# current_sensor.net
KiCad netlist of a schematic drawn in EAGLE
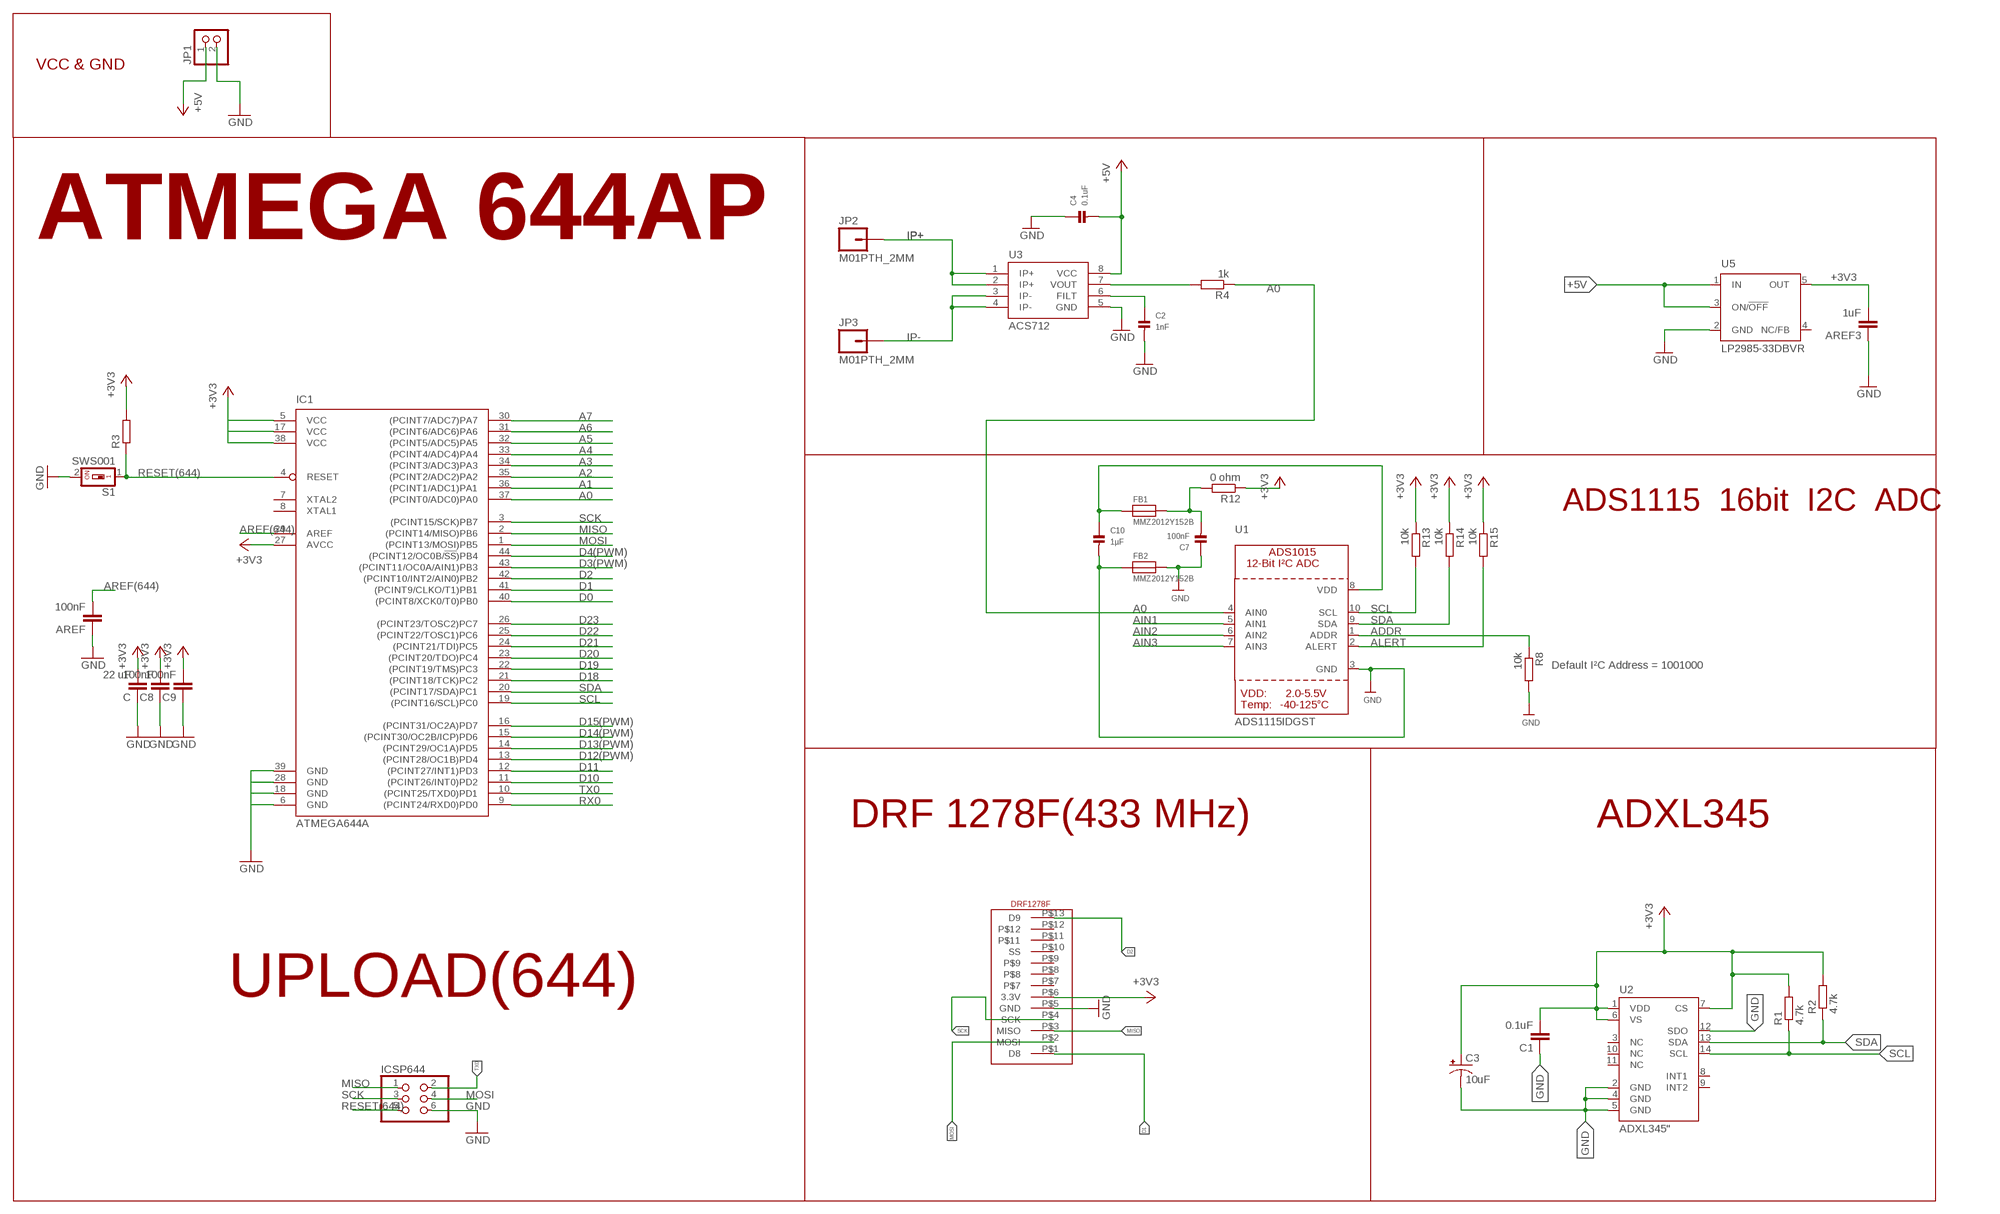
[diagram p0: schematic, sheet 1]

(export (version "E")
  (design (tool "Eeschema 10.0.6"))
  (components
    (comp (ref "AREF")
      (value "100nF")
      (footprint "eagle-import:C0805")
      (libsource (lib "eagle-import") (part "C-EUC0805"))
    )
    (comp (ref "AREF3")
      (value "1uF")
      (footprint "eagle-import:C0805")
      (libsource (lib "eagle-import") (part "C-EUC0805"))
    )
    (comp (ref "C")
      (value "22 uF")
      (footprint "eagle-import:C0805")
      (libsource (lib "eagle-import") (part "C-EUC0805"))
    )
    (comp (ref "C1")
      (value "0.1uF")
      (footprint "eagle-import:C0805")
      (libsource (lib "eagle-import") (part "C-EUC0805"))
    )
    (comp (ref "C2")
      (value "1nF")
      (footprint "eagle-import:0805")
      (libsource (lib "eagle-import") (part "CAP_CERAMIC0805"))
    )
    (comp (ref "C3")
      (value "10uF")
      (footprint "eagle-import:EIA3216")
      (libsource (lib "eagle-import") (part "CAP_POL1206"))
    )
    (comp (ref "C4")
      (value "0.1uF")
      (footprint "eagle-import:0805")
      (libsource (lib "eagle-import") (part "CAP_CERAMIC0805"))
    )
    (comp (ref "C7")
      (value "100nF")
      (footprint "eagle-import:0805")
      (libsource (lib "eagle-import") (part "CAP_CERAMIC0805"))
    )
    (comp (ref "C8")
      (value "100nF")
      (footprint "eagle-import:C0805")
      (libsource (lib "eagle-import") (part "C-EUC0805"))
    )
    (comp (ref "C9")
      (value "100nF")
      (footprint "eagle-import:C0805")
      (libsource (lib "eagle-import") (part "C-EUC0805"))
    )
    (comp (ref "C10")
      (value "1µF")
      (footprint "eagle-import:0805")
      (libsource (lib "eagle-import") (part "CAP_CERAMIC0805"))
    )
    (comp (ref "FB1")
      (value "MMZ2012Y152B")
      (footprint "eagle-import:0805")
      (libsource (lib "eagle-import") (part "FERRITE0805"))
    )
    (comp (ref "FB2")
      (value "MMZ2012Y152B")
      (footprint "eagle-import:0805")
      (libsource (lib "eagle-import") (part "FERRITE0805"))
    )
    (comp (ref "IC1")
      (value "ATMEGA644A")
      (footprint "eagle-import:TQFP44")
      (fields (field (name "MPN") "ATMEGA644PV-10AU"))
      (libsource (lib "eagle-import") (part "ATMEGA644A"))
    )
    (comp (ref "ICSP644")
      (value "PINHD-2X3")
      (footprint "eagle-import:2X03")
      (libsource (lib "eagle-import") (part "PINHD-2X3"))
    )
    (comp (ref "JP1")
      (value "PINHD-1X2")
      (footprint "eagle-import:1X02")
      (libsource (lib "eagle-import") (part "PINHD-1X2"))
    )
    (comp (ref "JP2")
      (value "M01PTH_2MM")
      (footprint "eagle-import:1X01_2MM")
      (libsource (lib "eagle-import") (part "M01PTH_2MM"))
    )
    (comp (ref "JP3")
      (value "M01PTH_2MM")
      (footprint "eagle-import:1X01_2MM")
      (libsource (lib "eagle-import") (part "M01PTH_2MM"))
    )
    (comp (ref "R1")
      (value "4.7k")
      (footprint "eagle-import:R0805")
      (libsource (lib "eagle-import") (part "R-EU_R0805"))
    )
    (comp (ref "R2")
      (value "4.7k")
      (footprint "eagle-import:R0805")
      (libsource (lib "eagle-import") (part "R-EU_R0805"))
    )
    (comp (ref "R3")
      (value "R-EU_R0805")
      (footprint "eagle-import:R0805")
      (libsource (lib "eagle-import") (part "R-EU_R0805"))
    )
    (comp (ref "R4")
      (value "1k")
      (footprint "eagle-import:R0805")
      (libsource (lib "eagle-import") (part "R-EU_R0805"))
    )
    (comp (ref "R8")
      (value "10k")
      (footprint "eagle-import:R0805")
      (libsource (lib "eagle-import") (part "R-EU_R0805"))
    )
    (comp (ref "R12")
      (value "0 ohm")
      (footprint "eagle-import:R0805")
      (libsource (lib "eagle-import") (part "R-EU_R0805"))
    )
    (comp (ref "R13")
      (value "10k")
      (footprint "eagle-import:R0805")
      (libsource (lib "eagle-import") (part "R-EU_R0805"))
    )
    (comp (ref "R14")
      (value "10k")
      (footprint "eagle-import:R0805")
      (libsource (lib "eagle-import") (part "R-EU_R0805"))
    )
    (comp (ref "R15")
      (value "10k")
      (footprint "eagle-import:R0805")
      (libsource (lib "eagle-import") (part "R-EU_R0805"))
    )
    (comp (ref "S1")
      (value "SWS001")
      (footprint "eagle-import:SMS-001")
      (libsource (lib "eagle-import") (part "SWS001"))
    )
    (comp (ref "U$1")
      (value "DRF1278F")
      (footprint "eagle-import:DIP13")
      (libsource (lib "eagle-import") (part "DRF1278F"))
    )
    (comp (ref "U1")
      (value "ADS1115IDGST")
      (footprint "eagle-import:MSOP10")
      (libsource (lib "eagle-import") (part "ADC_ADS1015"))
    )
    (comp (ref "U2")
      (value "ADXL345\"")
      (footprint "eagle-import:ADXL3451_1")
      (libsource (lib "eagle-import") (part "ADXL345{dblquote}"))
    )
    (comp (ref "U3")
      (value "ACS712")
      (footprint "eagle-import:SO08")
      (libsource (lib "eagle-import") (part "ACS712"))
    )
    (comp (ref "U5")
      (value "LP2985-33DBVR")
      (footprint "eagle-import:SOT23-DBV")
      (libsource (lib "eagle-import") (part "LP2985-XXDBVR33"))
    )
  )
  (nets
    (net (code "1") (name "+3V3") (class "Default")
      (node (ref "AREF3") (pin "2") (pinfunction "2_2") (pintype "passive"))
      (node (ref "C") (pin "2") (pinfunction "2_2") (pintype "passive"))
      (node (ref "C1") (pin "2") (pinfunction "2_2") (pintype "passive"))
      (node (ref "C3") (pin "A") (pinfunction "+_A") (pintype "passive"))
      (node (ref "C8") (pin "2") (pinfunction "2_2") (pintype "passive"))
      (node (ref "C9") (pin "2") (pinfunction "2_2") (pintype "passive"))
      (node (ref "IC1") (pin "17") (pinfunction "VCC_17") (pintype "power_in"))
      (node (ref "IC1") (pin "27") (pinfunction "AVCC_27") (pintype "power_in"))
      (node (ref "IC1") (pin "38") (pinfunction "VCC_38") (pintype "power_in"))
      (node (ref "IC1") (pin "5") (pinfunction "VCC_5") (pintype "power_in"))
      (node (ref "R1") (pin "2") (pinfunction "2_2") (pintype "passive"))
      (node (ref "R12") (pin "1") (pinfunction "1_1") (pintype "passive"))
      (node (ref "R13") (pin "1") (pinfunction "1_1") (pintype "passive"))
      (node (ref "R14") (pin "1") (pinfunction "1_1") (pintype "passive"))
      (node (ref "R15") (pin "1") (pinfunction "1_1") (pintype "passive"))
      (node (ref "R2") (pin "2") (pinfunction "2_2") (pintype "passive"))
      (node (ref "R3") (pin "2") (pinfunction "2_2") (pintype "passive"))
      (node (ref "U$1") (pin "P$6") (pinfunction "3.3V_P$6") (pintype "bidirectional"))
      (node (ref "U2") (pin "1") (pinfunction "VDD_1") (pintype "bidirectional"))
      (node (ref "U2") (pin "6") (pinfunction "VS_6") (pintype "bidirectional"))
      (node (ref "U2") (pin "7") (pinfunction "CS_7") (pintype "bidirectional"))
      (node (ref "U5") (pin "5") (pinfunction "OUT_5") (pintype "passive"))
    )
    (net (code "2") (name "+5V") (class "Default")
      (node (ref "C4") (pin "2") (pinfunction "P$2_2") (pintype "passive"))
      (node (ref "JP1") (pin "1") (pinfunction "1_1") (pintype "passive"))
      (node (ref "U3") (pin "8") (pinfunction "VCC_8") (pintype "bidirectional"))
      (node (ref "U5") (pin "1") (pinfunction "IN_1") (pintype "input"))
      (node (ref "U5") (pin "3") (pinfunction "ON/~{OFF}_3") (pintype "input"))
    )
    (net (code "3") (name "/A0") (class "Default")
      (node (ref "IC1") (pin "37") (pinfunction "(PCINT0/ADC0)PA0_37") (pintype "bidirectional"))
      (node (ref "R4") (pin "1") (pinfunction "1_1") (pintype "passive"))
      (node (ref "U1") (pin "4") (pinfunction "AIN0_4") (pintype "bidirectional"))
    )
    (net (code "4") (name "/A1") (class "Default")
      (node (ref "IC1") (pin "36") (pinfunction "(PCINT1/ADC1)PA1_36") (pintype "bidirectional"))
    )
    (net (code "5") (name "/A2") (class "Default")
      (node (ref "IC1") (pin "35") (pinfunction "(PCINT2/ADC2)PA2_35") (pintype "bidirectional"))
    )
    (net (code "6") (name "/A3") (class "Default")
      (node (ref "IC1") (pin "34") (pinfunction "(PCINT3/ADC3)PA3_34") (pintype "bidirectional"))
    )
    (net (code "7") (name "/A4") (class "Default")
      (node (ref "IC1") (pin "33") (pinfunction "(PCINT4/ADC4)PA4_33") (pintype "bidirectional"))
    )
    (net (code "8") (name "/A5") (class "Default")
      (node (ref "IC1") (pin "32") (pinfunction "(PCINT5/ADC5)PA5_32") (pintype "bidirectional"))
    )
    (net (code "9") (name "/A6") (class "Default")
      (node (ref "IC1") (pin "31") (pinfunction "(PCINT6/ADC6)PA6_31") (pintype "bidirectional"))
    )
    (net (code "10") (name "/A7") (class "Default")
      (node (ref "IC1") (pin "30") (pinfunction "(PCINT7/ADC7)PA7_30") (pintype "bidirectional"))
    )
    (net (code "11") (name "/ADDR") (class "Default")
      (node (ref "R8") (pin "1") (pinfunction "1_1") (pintype "passive"))
      (node (ref "U1") (pin "1") (pinfunction "ADDR_1") (pintype "bidirectional"))
    )
    (net (code "12") (name "/AIN1") (class "Default")
      (node (ref "U1") (pin "5") (pinfunction "AIN1_5") (pintype "bidirectional"))
    )
    (net (code "13") (name "/AIN2") (class "Default")
      (node (ref "U1") (pin "6") (pinfunction "AIN2_6") (pintype "bidirectional"))
    )
    (net (code "14") (name "/AIN3") (class "Default")
      (node (ref "U1") (pin "7") (pinfunction "AIN3_7") (pintype "bidirectional"))
    )
    (net (code "15") (name "/ALERT") (class "Default")
      (node (ref "R15") (pin "2") (pinfunction "2_2") (pintype "passive"))
      (node (ref "U1") (pin "2") (pinfunction "ALERT_2") (pintype "bidirectional"))
    )
    (net (code "16") (name "/AREF(644)") (class "Default")
      (node (ref "AREF") (pin "2") (pinfunction "2_2") (pintype "passive"))
      (node (ref "IC1") (pin "29") (pinfunction "AREF_29") (pintype "passive"))
    )
    (net (code "17") (name "/D0") (class "Default")
      (node (ref "IC1") (pin "40") (pinfunction "(PCINT8/XCK0/T0)PB0_40") (pintype "bidirectional"))
    )
    (net (code "18") (name "/D3(PWM)") (class "Default")
      (node (ref "IC1") (pin "43") (pinfunction "(PCINT11/OC0A/AIN1)PB3_43") (pintype "bidirectional"))
    )
    (net (code "19") (name "/D4(PWM)") (class "Default")
      (node (ref "IC1") (pin "44") (pinfunction "(PCINT12/OC0B/~{SS})PB4_44") (pintype "bidirectional"))
    )
    (net (code "20") (name "/D10") (class "Default")
      (node (ref "IC1") (pin "11") (pinfunction "(PCINT26/INT0)PD2_11") (pintype "bidirectional"))
    )
    (net (code "21") (name "/D11") (class "Default")
      (node (ref "IC1") (pin "12") (pinfunction "(PCINT27/INT1)PD3_12") (pintype "bidirectional"))
    )
    (net (code "22") (name "/D12(PWM)") (class "Default")
      (node (ref "IC1") (pin "13") (pinfunction "(PCINT28/OC1B)PD4_13") (pintype "bidirectional"))
    )
    (net (code "23") (name "/D13(PWM)") (class "Default")
      (node (ref "IC1") (pin "14") (pinfunction "(PCINT29/OC1A)PD5_14") (pintype "bidirectional"))
    )
    (net (code "24") (name "/D14(PWM)") (class "Default")
      (node (ref "IC1") (pin "15") (pinfunction "(PCINT30/OC2B/ICP)PD6_15") (pintype "bidirectional"))
    )
    (net (code "25") (name "/D15(PWM)") (class "Default")
      (node (ref "IC1") (pin "16") (pinfunction "(PCINT31/OC2A)PD7_16") (pintype "bidirectional"))
    )
    (net (code "26") (name "/D18") (class "Default")
      (node (ref "IC1") (pin "21") (pinfunction "(PCINT18/TCK)PC2_21") (pintype "output"))
    )
    (net (code "27") (name "/D19") (class "Default")
      (node (ref "IC1") (pin "22") (pinfunction "(PCINT19/TMS)PC3_22") (pintype "output"))
    )
    (net (code "28") (name "/D20") (class "Default")
      (node (ref "IC1") (pin "23") (pinfunction "(PCINT20/TDO)PC4_23") (pintype "output"))
    )
    (net (code "29") (name "/D21") (class "Default")
      (node (ref "IC1") (pin "24") (pinfunction "(PCINT21/TDI)PC5_24") (pintype "output"))
    )
    (net (code "30") (name "/D22") (class "Default")
      (node (ref "IC1") (pin "25") (pinfunction "(PCINT22/TOSC1)PC6_25") (pintype "output"))
    )
    (net (code "31") (name "/D23") (class "Default")
      (node (ref "IC1") (pin "26") (pinfunction "(PCINT23/TOSC2)PC7_26") (pintype "output"))
    )
    (net (code "32") (name "/IP+") (class "Default")
      (node (ref "JP2") (pin "1") (pinfunction "1_1") (pintype "passive"))
      (node (ref "U3") (pin "1") (pinfunction "IP+_1") (pintype "bidirectional"))
      (node (ref "U3") (pin "2") (pinfunction "IP+_2") (pintype "bidirectional"))
    )
    (net (code "33") (name "/IP-") (class "Default")
      (node (ref "JP3") (pin "1") (pinfunction "1_1") (pintype "passive"))
      (node (ref "U3") (pin "3") (pinfunction "IP-_3") (pintype "bidirectional"))
      (node (ref "U3") (pin "4") (pinfunction "IP-_4") (pintype "bidirectional"))
    )
    (net (code "34") (name "/RESET(644)") (class "Default")
      (node (ref "IC1") (pin "4") (pinfunction "RESET_4") (pintype "input"))
      (node (ref "ICSP644") (pin "5") (pinfunction "5_5") (pintype "passive"))
      (node (ref "R3") (pin "1") (pinfunction "1_1") (pintype "passive"))
      (node (ref "S1") (pin "1") (pinfunction "1_1") (pintype "passive"))
    )
    (net (code "35") (name "/RX0") (class "Default")
      (node (ref "IC1") (pin "9") (pinfunction "(PCINT24/RXD0)PD0_9") (pintype "bidirectional"))
    )
    (net (code "36") (name "D1") (class "Default")
      (node (ref "IC1") (pin "41") (pinfunction "(PCINT9/CLKO/T1)PB1_41") (pintype "bidirectional"))
      (node (ref "U$1") (pin "P$1") (pinfunction "D8_P$1") (pintype "bidirectional"))
    )
    (net (code "37") (name "D2") (class "Default")
      (node (ref "IC1") (pin "42") (pinfunction "(PCINT10/INT2/AIN0)PB2_42") (pintype "bidirectional"))
      (node (ref "U$1") (pin "P$13") (pinfunction "D9_P$13") (pintype "bidirectional"))
    )
    (net (code "38") (name "GND") (class "Default")
      (node (ref "AREF") (pin "1") (pinfunction "1_1") (pintype "passive"))
      (node (ref "AREF3") (pin "1") (pinfunction "1_1") (pintype "passive"))
      (node (ref "C") (pin "1") (pinfunction "1_1") (pintype "passive"))
      (node (ref "C1") (pin "1") (pinfunction "1_1") (pintype "passive"))
      (node (ref "C10") (pin "2") (pinfunction "P$2_2") (pintype "passive"))
      (node (ref "C2") (pin "2") (pinfunction "P$2_2") (pintype "passive"))
      (node (ref "C3") (pin "C") (pinfunction "-_C") (pintype "passive"))
      (node (ref "C4") (pin "1") (pinfunction "P$1_1") (pintype "passive"))
      (node (ref "C7") (pin "1") (pinfunction "P$1_1") (pintype "passive"))
      (node (ref "C8") (pin "1") (pinfunction "1_1") (pintype "passive"))
      (node (ref "C9") (pin "1") (pinfunction "1_1") (pintype "passive"))
      (node (ref "FB2") (pin "1") (pinfunction "P$1_1") (pintype "bidirectional"))
      (node (ref "FB2") (pin "2") (pinfunction "P$2_2") (pintype "bidirectional"))
      (node (ref "IC1") (pin "18") (pinfunction "GND_18") (pintype "power_in"))
      (node (ref "IC1") (pin "28") (pinfunction "GND_28") (pintype "power_in"))
      (node (ref "IC1") (pin "39") (pinfunction "GND_39") (pintype "power_in"))
      (node (ref "IC1") (pin "6") (pinfunction "GND_6") (pintype "power_in"))
      (node (ref "ICSP644") (pin "6") (pinfunction "6_6") (pintype "passive"))
      (node (ref "JP1") (pin "2") (pinfunction "2_2") (pintype "passive"))
      (node (ref "R8") (pin "2") (pinfunction "2_2") (pintype "passive"))
      (node (ref "S1") (pin "2") (pinfunction "2_2") (pintype "passive"))
      (node (ref "U$1") (pin "P$5") (pinfunction "GND_P$5") (pintype "bidirectional"))
      (node (ref "U1") (pin "3") (pinfunction "GND_3") (pintype "bidirectional"))
      (node (ref "U2") (pin "12") (pinfunction "SDO_12") (pintype "bidirectional"))
      (node (ref "U2") (pin "2") (pinfunction "GND_2") (pintype "bidirectional"))
      (node (ref "U2") (pin "4") (pinfunction "GND_4") (pintype "bidirectional"))
      (node (ref "U2") (pin "5") (pinfunction "GND_5") (pintype "bidirectional"))
      (node (ref "U3") (pin "5") (pinfunction "GND_5") (pintype "bidirectional"))
      (node (ref "U5") (pin "2") (pinfunction "GND_2") (pintype "power_in"))
    )
    (net (code "39") (name "MISO") (class "Default")
      (node (ref "IC1") (pin "2") (pinfunction "(PCINT14/MISO)PB6_2") (pintype "bidirectional"))
      (node (ref "ICSP644") (pin "1") (pinfunction "1_1") (pintype "passive"))
      (node (ref "U$1") (pin "P$3") (pinfunction "MISO_P$3") (pintype "bidirectional"))
    )
    (net (code "40") (name "MOSI") (class "Default")
      (node (ref "IC1") (pin "1") (pinfunction "(PCINT13/MOSI)PB5_1") (pintype "bidirectional"))
      (node (ref "ICSP644") (pin "4") (pinfunction "4_4") (pintype "passive"))
      (node (ref "U$1") (pin "P$2") (pinfunction "MOSI_P$2") (pintype "bidirectional"))
    )
    (net (code "41") (name "Net-(C2-P$1)") (class "Default")
      (node (ref "C2") (pin "1") (pinfunction "P$1_1") (pintype "passive"))
      (node (ref "U3") (pin "6") (pinfunction "FILT_6") (pintype "bidirectional"))
    )
    (net (code "42") (name "Net-(C7-P$2)") (class "Default")
      (node (ref "C7") (pin "2") (pinfunction "P$2_2") (pintype "passive"))
      (node (ref "FB1") (pin "2") (pinfunction "P$2_2") (pintype "bidirectional"))
      (node (ref "R12") (pin "2") (pinfunction "2_2") (pintype "passive"))
    )
    (net (code "43") (name "Net-(C10-P$1)") (class "Default")
      (node (ref "C10") (pin "1") (pinfunction "P$1_1") (pintype "passive"))
      (node (ref "FB1") (pin "1") (pinfunction "P$1_1") (pintype "bidirectional"))
      (node (ref "U1") (pin "8") (pinfunction "VDD_8") (pintype "bidirectional"))
    )
    (net (code "44") (name "Net-(U3-VOUT)") (class "Default")
      (node (ref "R4") (pin "2") (pinfunction "2_2") (pintype "passive"))
      (node (ref "U3") (pin "7") (pinfunction "VOUT_7") (pintype "bidirectional"))
    )
    (net (code "45") (name "SCK") (class "Default")
      (node (ref "IC1") (pin "3") (pinfunction "(PCINT15/SCK)PB7_3") (pintype "bidirectional"))
      (node (ref "ICSP644") (pin "3") (pinfunction "3_3") (pintype "passive"))
      (node (ref "U$1") (pin "P$4") (pinfunction "SCK_P$4") (pintype "bidirectional"))
    )
    (net (code "46") (name "SCL") (class "Default")
      (node (ref "IC1") (pin "19") (pinfunction "(PCINT16/SCL)PC0_19") (pintype "output"))
      (node (ref "R1") (pin "1") (pinfunction "1_1") (pintype "passive"))
      (node (ref "R13") (pin "2") (pinfunction "2_2") (pintype "passive"))
      (node (ref "U1") (pin "10") (pinfunction "SCL_10") (pintype "bidirectional"))
      (node (ref "U2") (pin "14") (pinfunction "SCL_14") (pintype "bidirectional"))
    )
    (net (code "47") (name "SDA") (class "Default")
      (node (ref "IC1") (pin "20") (pinfunction "(PCINT17/SDA)PC1_20") (pintype "output"))
      (node (ref "R14") (pin "2") (pinfunction "2_2") (pintype "passive"))
      (node (ref "R2") (pin "1") (pinfunction "1_1") (pintype "passive"))
      (node (ref "U1") (pin "9") (pinfunction "SDA_9") (pintype "bidirectional"))
      (node (ref "U2") (pin "13") (pinfunction "SDA_13") (pintype "bidirectional"))
    )
    (net (code "48") (name "TX0") (class "Default")
      (node (ref "IC1") (pin "10") (pinfunction "(PCINT25/TXD0)PD1_10") (pintype "bidirectional"))
      (node (ref "ICSP644") (pin "2") (pinfunction "2_2") (pintype "passive"))
    )
    (net (code "49") (name "unconnected-(IC1-XTAL1-Pad8)") (class "Default")
      (node (ref "IC1") (pin "8") (pinfunction "XTAL1_8") (pintype "bidirectional"))
    )
    (net (code "50") (name "unconnected-(IC1-XTAL2-Pad7)") (class "Default")
      (node (ref "IC1") (pin "7") (pinfunction "XTAL2_7") (pintype "bidirectional"))
    )
    (net (code "51") (name "unconnected-(U$1-PadP$7)") (class "Default")
      (node (ref "U$1") (pin "P$7") (pinfunction "P$7_P$7") (pintype "bidirectional"))
    )
    (net (code "52") (name "unconnected-(U$1-PadP$8)") (class "Default")
      (node (ref "U$1") (pin "P$8") (pinfunction "P$8_P$8") (pintype "bidirectional"))
    )
    (net (code "53") (name "unconnected-(U$1-PadP$9)") (class "Default")
      (node (ref "U$1") (pin "P$9") (pinfunction "P$9_P$9") (pintype "bidirectional"))
    )
    (net (code "54") (name "unconnected-(U$1-PadP$11)") (class "Default")
      (node (ref "U$1") (pin "P$11") (pinfunction "P$11_P$11") (pintype "bidirectional"))
    )
    (net (code "55") (name "unconnected-(U$1-PadP$12)") (class "Default")
      (node (ref "U$1") (pin "P$12") (pinfunction "P$12_P$12") (pintype "bidirectional"))
    )
    (net (code "56") (name "unconnected-(U$1-SS-PadP$10)") (class "Default")
      (node (ref "U$1") (pin "P$10") (pinfunction "SS_P$10") (pintype "bidirectional"))
    )
    (net (code "57") (name "unconnected-(U2-INT1-Pad8)") (class "Default")
      (node (ref "U2") (pin "8") (pinfunction "INT1_8") (pintype "bidirectional"))
    )
    (net (code "58") (name "unconnected-(U2-INT2-Pad9)") (class "Default")
      (node (ref "U2") (pin "9") (pinfunction "INT2_9") (pintype "bidirectional"))
    )
    (net (code "59") (name "unconnected-(U2-NC-Pad3)") (class "Default")
      (node (ref "U2") (pin "3") (pinfunction "NC_3") (pintype "bidirectional"))
    )
    (net (code "60") (name "unconnected-(U2-NC-Pad10)") (class "Default")
      (node (ref "U2") (pin "10") (pinfunction "NC_10") (pintype "bidirectional"))
    )
    (net (code "61") (name "unconnected-(U2-NC-Pad11)") (class "Default")
      (node (ref "U2") (pin "11") (pinfunction "NC_11") (pintype "bidirectional"))
    )
    (net (code "62") (name "unconnected-(U5-NC{slash}FB-Pad4)") (class "Default")
      (node (ref "U5") (pin "4") (pinfunction "NC/FB_4") (pintype "passive"))
    )
  )
)
